# R284B.net
KiCad netlist of a schematic drawn in EAGLE
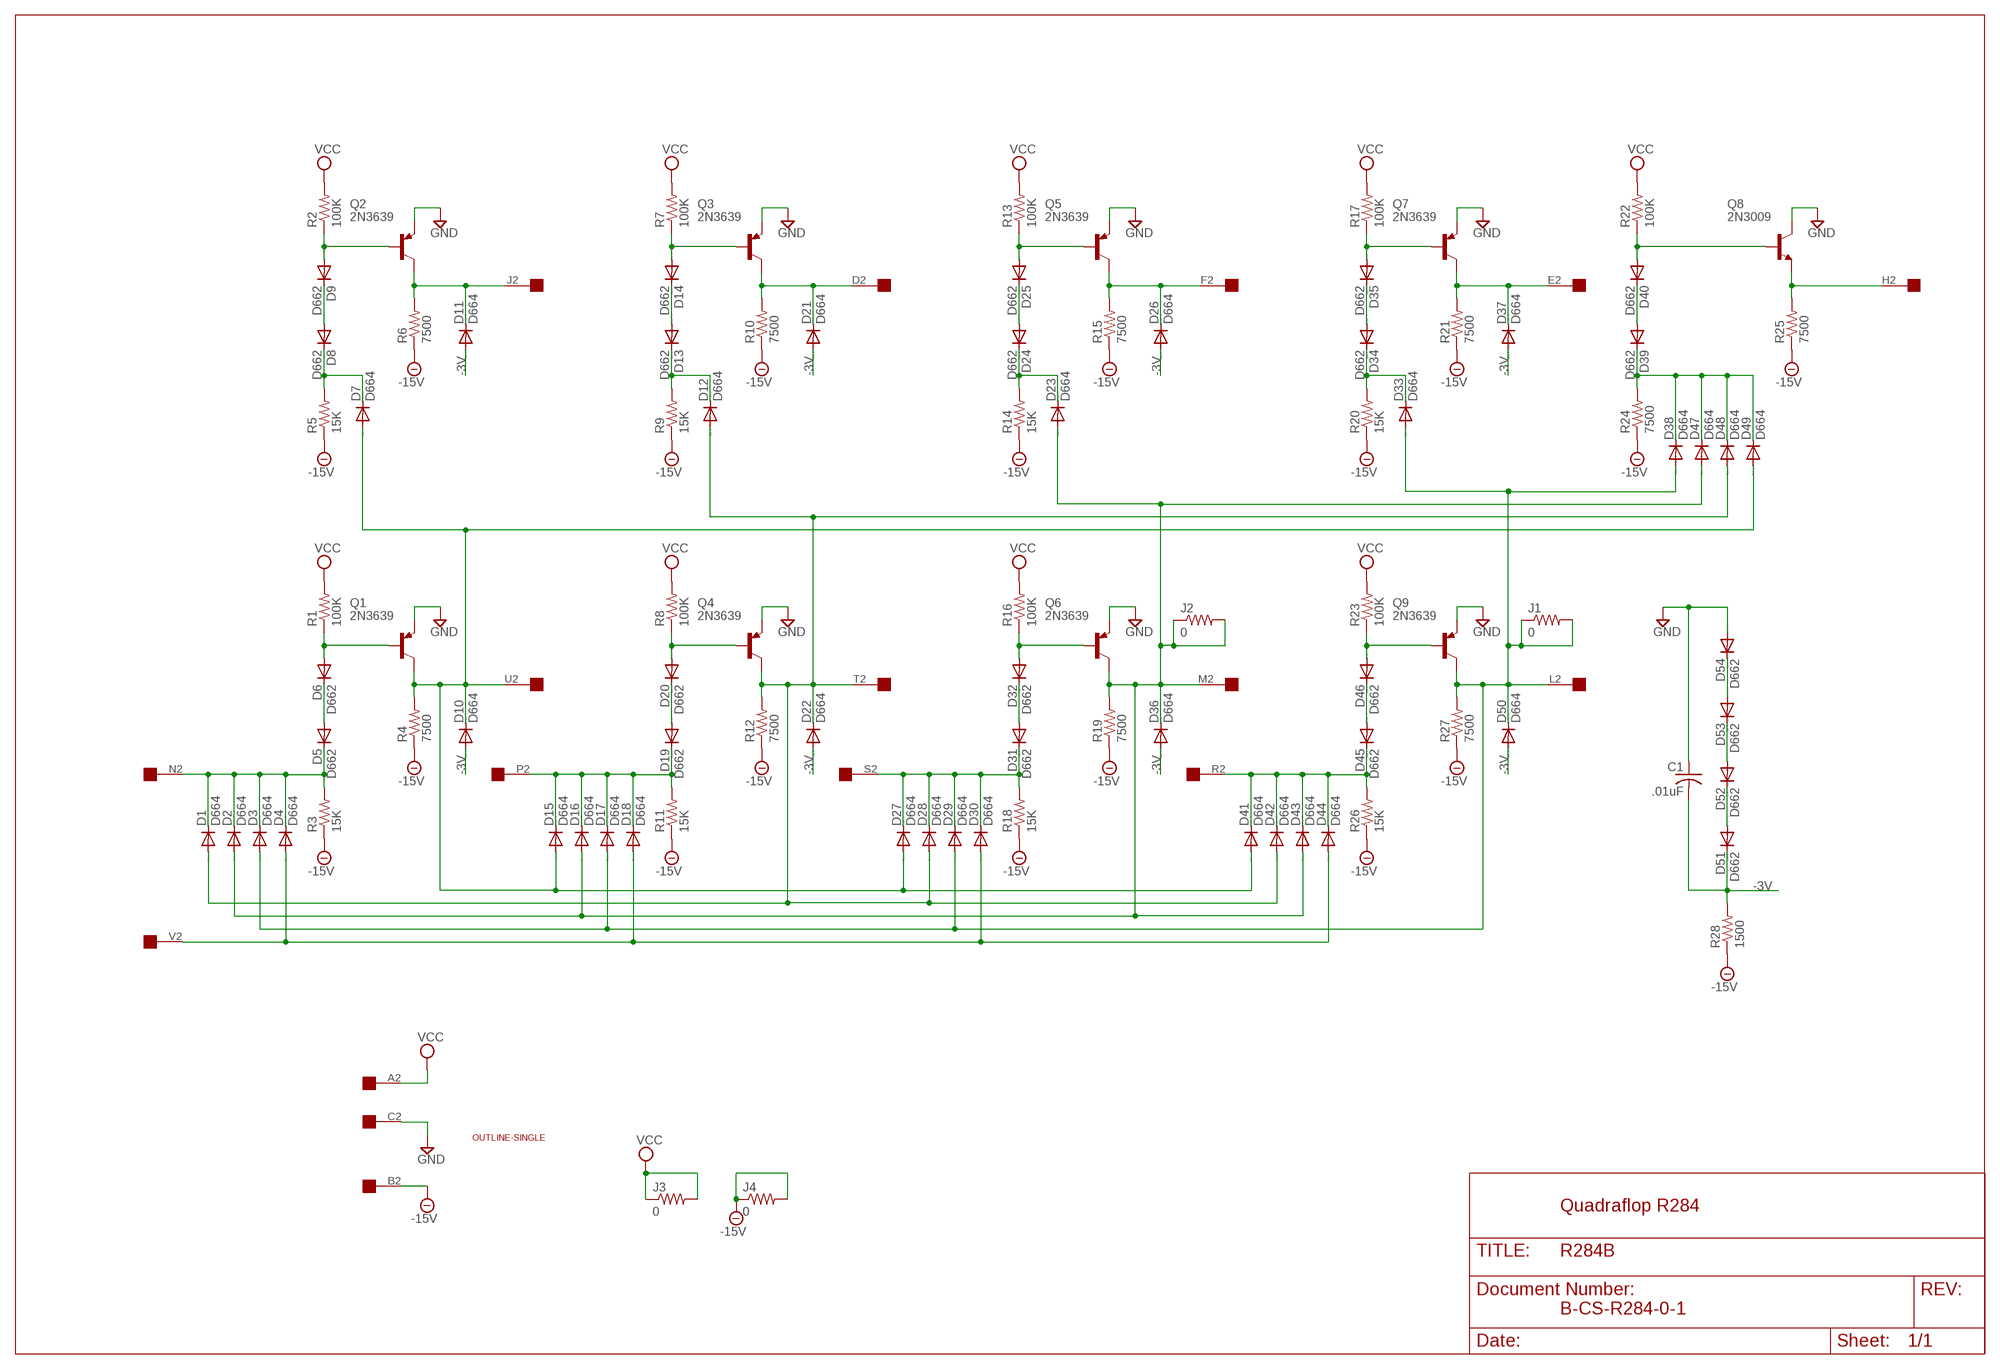
[diagram p0: schematic, sheet 1]

(export (version "E")
  (design (tool "Eeschema 10.0.6"))
  (components
    (comp (ref "C1")
      (value ".01uF")
      (footprint "eagle-import:C063-025X075")
      (libsource (lib "eagle-import") (part "C-US"))
    )
    (comp (ref "D1")
      (value "D664")
      (footprint "eagle-import:DO35-10")
      (libsource (lib "eagle-import") (part "DIODE-DO35-10"))
    )
    (comp (ref "D2")
      (value "D664")
      (footprint "eagle-import:DO35-10")
      (libsource (lib "eagle-import") (part "DIODE-DO35-10"))
    )
    (comp (ref "D3")
      (value "D664")
      (footprint "eagle-import:DO35-10")
      (libsource (lib "eagle-import") (part "DIODE-DO35-10"))
    )
    (comp (ref "D4")
      (value "D664")
      (footprint "eagle-import:DO35-10")
      (libsource (lib "eagle-import") (part "DIODE-DO35-10"))
    )
    (comp (ref "D5")
      (value "D662")
      (footprint "eagle-import:DO35-10")
      (libsource (lib "eagle-import") (part "DIODE-DO35-10"))
    )
    (comp (ref "D6")
      (value "D662")
      (footprint "eagle-import:DO35-10")
      (libsource (lib "eagle-import") (part "DIODE-DO35-10"))
    )
    (comp (ref "D7")
      (value "D664")
      (footprint "eagle-import:DO35-10")
      (libsource (lib "eagle-import") (part "DIODE-DO35-10"))
    )
    (comp (ref "D8")
      (value "D662")
      (footprint "eagle-import:DO35-10")
      (libsource (lib "eagle-import") (part "DIODE-DO35-10"))
    )
    (comp (ref "D9")
      (value "D662")
      (footprint "eagle-import:DO35-10")
      (libsource (lib "eagle-import") (part "DIODE-DO35-10"))
    )
    (comp (ref "D10")
      (value "D664")
      (footprint "eagle-import:DO35-10")
      (libsource (lib "eagle-import") (part "DIODE-DO35-10"))
    )
    (comp (ref "D11")
      (value "D664")
      (footprint "eagle-import:DO35-10")
      (libsource (lib "eagle-import") (part "DIODE-DO35-10"))
    )
    (comp (ref "D12")
      (value "D664")
      (footprint "eagle-import:DO35-10")
      (libsource (lib "eagle-import") (part "DIODE-DO35-10"))
    )
    (comp (ref "D13")
      (value "D662")
      (footprint "eagle-import:DO35-10")
      (libsource (lib "eagle-import") (part "DIODE-DO35-10"))
    )
    (comp (ref "D14")
      (value "D662")
      (footprint "eagle-import:DO35-10")
      (libsource (lib "eagle-import") (part "DIODE-DO35-10"))
    )
    (comp (ref "D15")
      (value "D664")
      (footprint "eagle-import:DO35-10")
      (libsource (lib "eagle-import") (part "DIODE-DO35-10"))
    )
    (comp (ref "D16")
      (value "D664")
      (footprint "eagle-import:DO35-10")
      (libsource (lib "eagle-import") (part "DIODE-DO35-10"))
    )
    (comp (ref "D17")
      (value "D664")
      (footprint "eagle-import:DO35-10")
      (libsource (lib "eagle-import") (part "DIODE-DO35-10"))
    )
    (comp (ref "D18")
      (value "D664")
      (footprint "eagle-import:DO35-10")
      (libsource (lib "eagle-import") (part "DIODE-DO35-10"))
    )
    (comp (ref "D19")
      (value "D662")
      (footprint "eagle-import:DO35-10")
      (libsource (lib "eagle-import") (part "DIODE-DO35-10"))
    )
    (comp (ref "D20")
      (value "D662")
      (footprint "eagle-import:DO35-10")
      (libsource (lib "eagle-import") (part "DIODE-DO35-10"))
    )
    (comp (ref "D21")
      (value "D664")
      (footprint "eagle-import:DO35-10")
      (libsource (lib "eagle-import") (part "DIODE-DO35-10"))
    )
    (comp (ref "D22")
      (value "D664")
      (footprint "eagle-import:DO35-10")
      (libsource (lib "eagle-import") (part "DIODE-DO35-10"))
    )
    (comp (ref "D23")
      (value "D664")
      (footprint "eagle-import:DO35-10")
      (libsource (lib "eagle-import") (part "DIODE-DO35-10"))
    )
    (comp (ref "D24")
      (value "D662")
      (footprint "eagle-import:DO35-10")
      (libsource (lib "eagle-import") (part "DIODE-DO35-10"))
    )
    (comp (ref "D25")
      (value "D662")
      (footprint "eagle-import:DO35-10")
      (libsource (lib "eagle-import") (part "DIODE-DO35-10"))
    )
    (comp (ref "D26")
      (value "D664")
      (footprint "eagle-import:DO35-10")
      (libsource (lib "eagle-import") (part "DIODE-DO35-10"))
    )
    (comp (ref "D27")
      (value "D664")
      (footprint "eagle-import:DO35-10")
      (libsource (lib "eagle-import") (part "DIODE-DO35-10"))
    )
    (comp (ref "D28")
      (value "D664")
      (footprint "eagle-import:DO35-10")
      (libsource (lib "eagle-import") (part "DIODE-DO35-10"))
    )
    (comp (ref "D29")
      (value "D664")
      (footprint "eagle-import:DO35-10")
      (libsource (lib "eagle-import") (part "DIODE-DO35-10"))
    )
    (comp (ref "D30")
      (value "D664")
      (footprint "eagle-import:DO35-10")
      (libsource (lib "eagle-import") (part "DIODE-DO35-10"))
    )
    (comp (ref "D31")
      (value "D662")
      (footprint "eagle-import:DO35-10")
      (libsource (lib "eagle-import") (part "DIODE-DO35-10"))
    )
    (comp (ref "D32")
      (value "D662")
      (footprint "eagle-import:DO35-10")
      (libsource (lib "eagle-import") (part "DIODE-DO35-10"))
    )
    (comp (ref "D33")
      (value "D664")
      (footprint "eagle-import:DO35-10")
      (libsource (lib "eagle-import") (part "DIODE-DO35-10"))
    )
    (comp (ref "D34")
      (value "D662")
      (footprint "eagle-import:DO35-10")
      (libsource (lib "eagle-import") (part "DIODE-DO35-10"))
    )
    (comp (ref "D35")
      (value "D662")
      (footprint "eagle-import:DO35-10")
      (libsource (lib "eagle-import") (part "DIODE-DO35-10"))
    )
    (comp (ref "D36")
      (value "D664")
      (footprint "eagle-import:DO35-10")
      (libsource (lib "eagle-import") (part "DIODE-DO35-10"))
    )
    (comp (ref "D37")
      (value "D664")
      (footprint "eagle-import:DO35-10")
      (libsource (lib "eagle-import") (part "DIODE-DO35-10"))
    )
    (comp (ref "D38")
      (value "D664")
      (footprint "eagle-import:DO35-10")
      (libsource (lib "eagle-import") (part "DIODE-DO35-10"))
    )
    (comp (ref "D39")
      (value "D662")
      (footprint "eagle-import:DO35-10")
      (libsource (lib "eagle-import") (part "DIODE-DO35-10"))
    )
    (comp (ref "D40")
      (value "D662")
      (footprint "eagle-import:DO35-10")
      (libsource (lib "eagle-import") (part "DIODE-DO35-10"))
    )
    (comp (ref "D41")
      (value "D664")
      (footprint "eagle-import:DO35-10")
      (libsource (lib "eagle-import") (part "DIODE-DO35-10"))
    )
    (comp (ref "D42")
      (value "D664")
      (footprint "eagle-import:DO35-10")
      (libsource (lib "eagle-import") (part "DIODE-DO35-10"))
    )
    (comp (ref "D43")
      (value "D664")
      (footprint "eagle-import:DO35-10")
      (libsource (lib "eagle-import") (part "DIODE-DO35-10"))
    )
    (comp (ref "D44")
      (value "D664")
      (footprint "eagle-import:DO35-10")
      (libsource (lib "eagle-import") (part "DIODE-DO35-10"))
    )
    (comp (ref "D45")
      (value "D662")
      (footprint "eagle-import:DO35-10")
      (libsource (lib "eagle-import") (part "DIODE-DO35-10"))
    )
    (comp (ref "D46")
      (value "D662")
      (footprint "eagle-import:DO35-10")
      (libsource (lib "eagle-import") (part "DIODE-DO35-10"))
    )
    (comp (ref "D47")
      (value "D664")
      (footprint "eagle-import:DO35-10")
      (libsource (lib "eagle-import") (part "DIODE-DO35-10"))
    )
    (comp (ref "D48")
      (value "D664")
      (footprint "eagle-import:DO35-10")
      (libsource (lib "eagle-import") (part "DIODE-DO35-10"))
    )
    (comp (ref "D49")
      (value "D664")
      (footprint "eagle-import:DO35-10")
      (libsource (lib "eagle-import") (part "DIODE-DO35-10"))
    )
    (comp (ref "D50")
      (value "D664")
      (footprint "eagle-import:DO35-10")
      (libsource (lib "eagle-import") (part "DIODE-DO35-10"))
    )
    (comp (ref "D51")
      (value "D662")
      (footprint "eagle-import:DO35-10")
      (libsource (lib "eagle-import") (part "DIODE-DO35-10"))
    )
    (comp (ref "D52")
      (value "D662")
      (footprint "eagle-import:DO35-10")
      (libsource (lib "eagle-import") (part "DIODE-DO35-10"))
    )
    (comp (ref "D53")
      (value "D662")
      (footprint "eagle-import:DO35-10")
      (libsource (lib "eagle-import") (part "DIODE-DO35-10"))
    )
    (comp (ref "D54")
      (value "D662")
      (footprint "eagle-import:DO35-10")
      (libsource (lib "eagle-import") (part "DIODE-DO35-10"))
    )
    (comp (ref "J1")
      (value "0")
      (footprint "eagle-import:0207_10")
      (libsource (lib "eagle-import") (part "R-US_0207/10"))
    )
    (comp (ref "J2")
      (value "0")
      (footprint "eagle-import:0207_10")
      (libsource (lib "eagle-import") (part "R-US_0207/10"))
    )
    (comp (ref "J3")
      (value "0")
      (footprint "eagle-import:0207_10")
      (libsource (lib "eagle-import") (part "R-US_0207/10"))
    )
    (comp (ref "J4")
      (value "0")
      (footprint "eagle-import:0207_10")
      (libsource (lib "eagle-import") (part "R-US_0207/10"))
    )
    (comp (ref "Q1")
      (value "2N3639")
      (footprint "eagle-import:TO5")
      (libsource (lib "eagle-import") (part "-PNP-TO5"))
    )
    (comp (ref "Q2")
      (value "2N3639")
      (footprint "eagle-import:TO5")
      (libsource (lib "eagle-import") (part "-PNP-TO5"))
    )
    (comp (ref "Q3")
      (value "2N3639")
      (footprint "eagle-import:TO5")
      (libsource (lib "eagle-import") (part "-PNP-TO5"))
    )
    (comp (ref "Q4")
      (value "2N3639")
      (footprint "eagle-import:TO5")
      (libsource (lib "eagle-import") (part "-PNP-TO5"))
    )
    (comp (ref "Q5")
      (value "2N3639")
      (footprint "eagle-import:TO5")
      (libsource (lib "eagle-import") (part "-PNP-TO5"))
    )
    (comp (ref "Q6")
      (value "2N3639")
      (footprint "eagle-import:TO5")
      (libsource (lib "eagle-import") (part "-PNP-TO5"))
    )
    (comp (ref "Q7")
      (value "2N3639")
      (footprint "eagle-import:TO5")
      (libsource (lib "eagle-import") (part "-PNP-TO5"))
    )
    (comp (ref "Q8")
      (value "2N3009")
      (footprint "eagle-import:TO5")
      (libsource (lib "eagle-import") (part "-NPN-TO5"))
    )
    (comp (ref "Q9")
      (value "2N3639")
      (footprint "eagle-import:TO5")
      (libsource (lib "eagle-import") (part "-PNP-TO5"))
    )
    (comp (ref "R1")
      (value "100K")
      (footprint "eagle-import:0207_10")
      (libsource (lib "eagle-import") (part "R-US_0207/10"))
    )
    (comp (ref "R2")
      (value "100K")
      (footprint "eagle-import:0207_10")
      (libsource (lib "eagle-import") (part "R-US_0207/10"))
    )
    (comp (ref "R3")
      (value "15K")
      (footprint "eagle-import:0207_10")
      (libsource (lib "eagle-import") (part "R-US_0207/10"))
    )
    (comp (ref "R4")
      (value "7500")
      (footprint "eagle-import:0207_10")
      (libsource (lib "eagle-import") (part "R-US_0207/10"))
    )
    (comp (ref "R5")
      (value "15K")
      (footprint "eagle-import:0207_10")
      (libsource (lib "eagle-import") (part "R-US_0207/10"))
    )
    (comp (ref "R6")
      (value "7500")
      (footprint "eagle-import:0207_10")
      (libsource (lib "eagle-import") (part "R-US_0207/10"))
    )
    (comp (ref "R7")
      (value "100K")
      (footprint "eagle-import:0207_10")
      (libsource (lib "eagle-import") (part "R-US_0207/10"))
    )
    (comp (ref "R8")
      (value "100K")
      (footprint "eagle-import:0207_10")
      (libsource (lib "eagle-import") (part "R-US_0207/10"))
    )
    (comp (ref "R9")
      (value "15K")
      (footprint "eagle-import:0207_10")
      (libsource (lib "eagle-import") (part "R-US_0207/10"))
    )
    (comp (ref "R10")
      (value "7500")
      (footprint "eagle-import:0207_10")
      (libsource (lib "eagle-import") (part "R-US_0207/10"))
    )
    (comp (ref "R11")
      (value "15K")
      (footprint "eagle-import:0207_10")
      (libsource (lib "eagle-import") (part "R-US_0207/10"))
    )
    (comp (ref "R12")
      (value "7500")
      (footprint "eagle-import:0207_10")
      (libsource (lib "eagle-import") (part "R-US_0207/10"))
    )
    (comp (ref "R13")
      (value "100K")
      (footprint "eagle-import:0207_10")
      (libsource (lib "eagle-import") (part "R-US_0207/10"))
    )
    (comp (ref "R14")
      (value "15K")
      (footprint "eagle-import:0207_10")
      (libsource (lib "eagle-import") (part "R-US_0207/10"))
    )
    (comp (ref "R15")
      (value "7500")
      (footprint "eagle-import:0207_10")
      (libsource (lib "eagle-import") (part "R-US_0207/10"))
    )
    (comp (ref "R16")
      (value "100K")
      (footprint "eagle-import:0207_10")
      (libsource (lib "eagle-import") (part "R-US_0207/10"))
    )
    (comp (ref "R17")
      (value "100K")
      (footprint "eagle-import:0207_10")
      (libsource (lib "eagle-import") (part "R-US_0207/10"))
    )
    (comp (ref "R18")
      (value "15K")
      (footprint "eagle-import:0207_10")
      (libsource (lib "eagle-import") (part "R-US_0207/10"))
    )
    (comp (ref "R19")
      (value "7500")
      (footprint "eagle-import:0207_10")
      (libsource (lib "eagle-import") (part "R-US_0207/10"))
    )
    (comp (ref "R20")
      (value "15K")
      (footprint "eagle-import:0207_10")
      (libsource (lib "eagle-import") (part "R-US_0207/10"))
    )
    (comp (ref "R21")
      (value "7500")
      (footprint "eagle-import:0207_10")
      (libsource (lib "eagle-import") (part "R-US_0207/10"))
    )
    (comp (ref "R22")
      (value "100K")
      (footprint "eagle-import:0207_10")
      (libsource (lib "eagle-import") (part "R-US_0207/10"))
    )
    (comp (ref "R23")
      (value "100K")
      (footprint "eagle-import:0207_10")
      (libsource (lib "eagle-import") (part "R-US_0207/10"))
    )
    (comp (ref "R24")
      (value "7500")
      (footprint "eagle-import:0207_10")
      (libsource (lib "eagle-import") (part "R-US_0207/10"))
    )
    (comp (ref "R25")
      (value "7500")
      (footprint "eagle-import:0207_10")
      (libsource (lib "eagle-import") (part "R-US_0207/10"))
    )
    (comp (ref "R26")
      (value "15K")
      (footprint "eagle-import:0207_10")
      (libsource (lib "eagle-import") (part "R-US_0207/10"))
    )
    (comp (ref "R27")
      (value "7500")
      (footprint "eagle-import:0207_10")
      (libsource (lib "eagle-import") (part "R-US_0207/10"))
    )
    (comp (ref "R28")
      (value "1500")
      (footprint "eagle-import:0207_10")
      (libsource (lib "eagle-import") (part "R-US_0207/10"))
    )
    (comp (ref "U$1")
      (value "OUTLINE-SINGLE")
      (footprint "eagle-import:SINGLE")
      (libsource (lib "eagle-import") (part "OUTLINE-SINGLE"))
    )
    (comp (ref "U$2")
      (value "EDGE-1")
      (footprint "eagle-import:EDGE-CON1")
      (libsource (lib "eagle-import") (part "EDGE-1"))
    )
  )
  (nets
    (net (code "1") (name "-15V") (class "Default")
      (node (ref "J4") (pin "1") (pinfunction "1_1") (pintype "passive"))
      (node (ref "J4") (pin "2") (pinfunction "2_2") (pintype "passive"))
      (node (ref "R10") (pin "1") (pinfunction "1_1") (pintype "passive"))
      (node (ref "R11") (pin "1") (pinfunction "1_1") (pintype "passive"))
      (node (ref "R12") (pin "1") (pinfunction "1_1") (pintype "passive"))
      (node (ref "R14") (pin "1") (pinfunction "1_1") (pintype "passive"))
      (node (ref "R15") (pin "1") (pinfunction "1_1") (pintype "passive"))
      (node (ref "R18") (pin "1") (pinfunction "1_1") (pintype "passive"))
      (node (ref "R19") (pin "1") (pinfunction "1_1") (pintype "passive"))
      (node (ref "R20") (pin "1") (pinfunction "1_1") (pintype "passive"))
      (node (ref "R21") (pin "1") (pinfunction "1_1") (pintype "passive"))
      (node (ref "R24") (pin "1") (pinfunction "1_1") (pintype "passive"))
      (node (ref "R25") (pin "1") (pinfunction "1_1") (pintype "passive"))
      (node (ref "R26") (pin "1") (pinfunction "1_1") (pintype "passive"))
      (node (ref "R27") (pin "1") (pinfunction "1_1") (pintype "passive"))
      (node (ref "R28") (pin "1") (pinfunction "1_1") (pintype "passive"))
      (node (ref "R3") (pin "1") (pinfunction "1_1") (pintype "passive"))
      (node (ref "R4") (pin "1") (pinfunction "1_1") (pintype "passive"))
      (node (ref "R5") (pin "1") (pinfunction "1_1") (pintype "passive"))
      (node (ref "R6") (pin "1") (pinfunction "1_1") (pintype "passive"))
      (node (ref "R9") (pin "1") (pinfunction "1_1") (pintype "passive"))
      (node (ref "U$2") (pin "B2") (pinfunction "1_B2") (pintype "bidirectional"))
    )
    (net (code "2") (name "/-3V") (class "Default")
      (node (ref "C1") (pin "2") (pinfunction "2_2") (pintype "passive"))
      (node (ref "D10") (pin "A") (pinfunction "A_A") (pintype "passive"))
      (node (ref "D11") (pin "A") (pinfunction "A_A") (pintype "passive"))
      (node (ref "D21") (pin "A") (pinfunction "A_A") (pintype "passive"))
      (node (ref "D22") (pin "A") (pinfunction "A_A") (pintype "passive"))
      (node (ref "D26") (pin "A") (pinfunction "A_A") (pintype "passive"))
      (node (ref "D36") (pin "A") (pinfunction "A_A") (pintype "passive"))
      (node (ref "D37") (pin "A") (pinfunction "A_A") (pintype "passive"))
      (node (ref "D50") (pin "A") (pinfunction "A_A") (pintype "passive"))
      (node (ref "D51") (pin "C") (pinfunction "C_C") (pintype "passive"))
      (node (ref "R28") (pin "2") (pinfunction "2_2") (pintype "passive"))
    )
    (net (code "3") (name "GND") (class "Default")
      (node (ref "C1") (pin "1") (pinfunction "1_1") (pintype "passive"))
      (node (ref "D54") (pin "A") (pinfunction "A_A") (pintype "passive"))
      (node (ref "Q1") (pin "1") (pinfunction "E_1") (pintype "passive"))
      (node (ref "Q2") (pin "1") (pinfunction "E_1") (pintype "passive"))
      (node (ref "Q3") (pin "1") (pinfunction "E_1") (pintype "passive"))
      (node (ref "Q4") (pin "1") (pinfunction "E_1") (pintype "passive"))
      (node (ref "Q5") (pin "1") (pinfunction "E_1") (pintype "passive"))
      (node (ref "Q6") (pin "1") (pinfunction "E_1") (pintype "passive"))
      (node (ref "Q7") (pin "1") (pinfunction "E_1") (pintype "passive"))
      (node (ref "Q8") (pin "3") (pinfunction "C_3") (pintype "passive"))
      (node (ref "Q9") (pin "1") (pinfunction "E_1") (pintype "passive"))
      (node (ref "U$2") (pin "C2") (pinfunction "1_C2") (pintype "bidirectional"))
    )
    (net (code "4") (name "Net-(D5-PadA)") (class "Default")
      (node (ref "D5") (pin "A") (pinfunction "A_A") (pintype "passive"))
      (node (ref "D6") (pin "C") (pinfunction "C_C") (pintype "passive"))
    )
    (net (code "5") (name "Net-(D7-PadC)") (class "Default")
      (node (ref "D7") (pin "C") (pinfunction "C_C") (pintype "passive"))
      (node (ref "D8") (pin "C") (pinfunction "C_C") (pintype "passive"))
      (node (ref "R5") (pin "2") (pinfunction "2_2") (pintype "passive"))
    )
    (net (code "6") (name "Net-(D8-PadA)") (class "Default")
      (node (ref "D8") (pin "A") (pinfunction "A_A") (pintype "passive"))
      (node (ref "D9") (pin "C") (pinfunction "C_C") (pintype "passive"))
    )
    (net (code "7") (name "Net-(D12-PadC)") (class "Default")
      (node (ref "D12") (pin "C") (pinfunction "C_C") (pintype "passive"))
      (node (ref "D13") (pin "C") (pinfunction "C_C") (pintype "passive"))
      (node (ref "R9") (pin "2") (pinfunction "2_2") (pintype "passive"))
    )
    (net (code "8") (name "Net-(D13-PadA)") (class "Default")
      (node (ref "D13") (pin "A") (pinfunction "A_A") (pintype "passive"))
      (node (ref "D14") (pin "C") (pinfunction "C_C") (pintype "passive"))
    )
    (net (code "9") (name "Net-(D19-PadA)") (class "Default")
      (node (ref "D19") (pin "A") (pinfunction "A_A") (pintype "passive"))
      (node (ref "D20") (pin "C") (pinfunction "C_C") (pintype "passive"))
    )
    (net (code "10") (name "Net-(D23-PadC)") (class "Default")
      (node (ref "D23") (pin "C") (pinfunction "C_C") (pintype "passive"))
      (node (ref "D24") (pin "C") (pinfunction "C_C") (pintype "passive"))
      (node (ref "R14") (pin "2") (pinfunction "2_2") (pintype "passive"))
    )
    (net (code "11") (name "Net-(D24-PadA)") (class "Default")
      (node (ref "D24") (pin "A") (pinfunction "A_A") (pintype "passive"))
      (node (ref "D25") (pin "C") (pinfunction "C_C") (pintype "passive"))
    )
    (net (code "12") (name "Net-(D31-PadA)") (class "Default")
      (node (ref "D31") (pin "A") (pinfunction "A_A") (pintype "passive"))
      (node (ref "D32") (pin "C") (pinfunction "C_C") (pintype "passive"))
    )
    (net (code "13") (name "Net-(D33-PadC)") (class "Default")
      (node (ref "D33") (pin "C") (pinfunction "C_C") (pintype "passive"))
      (node (ref "D34") (pin "C") (pinfunction "C_C") (pintype "passive"))
      (node (ref "R20") (pin "2") (pinfunction "2_2") (pintype "passive"))
    )
    (net (code "14") (name "Net-(D34-PadA)") (class "Default")
      (node (ref "D34") (pin "A") (pinfunction "A_A") (pintype "passive"))
      (node (ref "D35") (pin "C") (pinfunction "C_C") (pintype "passive"))
    )
    (net (code "15") (name "Net-(D38-PadC)") (class "Default")
      (node (ref "D38") (pin "C") (pinfunction "C_C") (pintype "passive"))
      (node (ref "D39") (pin "C") (pinfunction "C_C") (pintype "passive"))
      (node (ref "D47") (pin "C") (pinfunction "C_C") (pintype "passive"))
      (node (ref "D48") (pin "C") (pinfunction "C_C") (pintype "passive"))
      (node (ref "D49") (pin "C") (pinfunction "C_C") (pintype "passive"))
      (node (ref "R24") (pin "2") (pinfunction "2_2") (pintype "passive"))
    )
    (net (code "16") (name "Net-(D39-PadA)") (class "Default")
      (node (ref "D39") (pin "A") (pinfunction "A_A") (pintype "passive"))
      (node (ref "D40") (pin "C") (pinfunction "C_C") (pintype "passive"))
    )
    (net (code "17") (name "Net-(D45-PadA)") (class "Default")
      (node (ref "D45") (pin "A") (pinfunction "A_A") (pintype "passive"))
      (node (ref "D46") (pin "C") (pinfunction "C_C") (pintype "passive"))
    )
    (net (code "18") (name "Net-(D51-PadA)") (class "Default")
      (node (ref "D51") (pin "A") (pinfunction "A_A") (pintype "passive"))
      (node (ref "D52") (pin "C") (pinfunction "C_C") (pintype "passive"))
    )
    (net (code "19") (name "Net-(D52-PadA)") (class "Default")
      (node (ref "D52") (pin "A") (pinfunction "A_A") (pintype "passive"))
      (node (ref "D53") (pin "C") (pinfunction "C_C") (pintype "passive"))
    )
    (net (code "20") (name "Net-(D53-PadA)") (class "Default")
      (node (ref "D53") (pin "A") (pinfunction "A_A") (pintype "passive"))
      (node (ref "D54") (pin "C") (pinfunction "C_C") (pintype "passive"))
    )
    (net (code "21") (name "Net-(Q1-B)") (class "Default")
      (node (ref "D6") (pin "A") (pinfunction "A_A") (pintype "passive"))
      (node (ref "Q1") (pin "2") (pinfunction "B_2") (pintype "passive"))
      (node (ref "R1") (pin "1") (pinfunction "1_1") (pintype "passive"))
    )
    (net (code "22") (name "Net-(Q1-C)") (class "Default")
      (node (ref "D10") (pin "C") (pinfunction "C_C") (pintype "passive"))
      (node (ref "D15") (pin "A") (pinfunction "A_A") (pintype "passive"))
      (node (ref "D27") (pin "A") (pinfunction "A_A") (pintype "passive"))
      (node (ref "D41") (pin "A") (pinfunction "A_A") (pintype "passive"))
      (node (ref "D49") (pin "A") (pinfunction "A_A") (pintype "passive"))
      (node (ref "D7") (pin "A") (pinfunction "A_A") (pintype "passive"))
      (node (ref "Q1") (pin "3") (pinfunction "C_3") (pintype "passive"))
      (node (ref "R4") (pin "2") (pinfunction "2_2") (pintype "passive"))
      (node (ref "U$2") (pin "U2") (pinfunction "1_U2") (pintype "bidirectional"))
    )
    (net (code "23") (name "Net-(Q2-B)") (class "Default")
      (node (ref "D9") (pin "A") (pinfunction "A_A") (pintype "passive"))
      (node (ref "Q2") (pin "2") (pinfunction "B_2") (pintype "passive"))
      (node (ref "R2") (pin "1") (pinfunction "1_1") (pintype "passive"))
    )
    (net (code "24") (name "Net-(Q2-C)") (class "Default")
      (node (ref "D11") (pin "C") (pinfunction "C_C") (pintype "passive"))
      (node (ref "Q2") (pin "3") (pinfunction "C_3") (pintype "passive"))
      (node (ref "R6") (pin "2") (pinfunction "2_2") (pintype "passive"))
      (node (ref "U$2") (pin "J2") (pinfunction "1_J2") (pintype "bidirectional"))
    )
    (net (code "25") (name "Net-(Q3-B)") (class "Default")
      (node (ref "D14") (pin "A") (pinfunction "A_A") (pintype "passive"))
      (node (ref "Q3") (pin "2") (pinfunction "B_2") (pintype "passive"))
      (node (ref "R7") (pin "1") (pinfunction "1_1") (pintype "passive"))
    )
    (net (code "26") (name "Net-(Q3-C)") (class "Default")
      (node (ref "D21") (pin "C") (pinfunction "C_C") (pintype "passive"))
      (node (ref "Q3") (pin "3") (pinfunction "C_3") (pintype "passive"))
      (node (ref "R10") (pin "2") (pinfunction "2_2") (pintype "passive"))
      (node (ref "U$2") (pin "D2") (pinfunction "1_D2") (pintype "bidirectional"))
    )
    (net (code "27") (name "Net-(Q4-B)") (class "Default")
      (node (ref "D20") (pin "A") (pinfunction "A_A") (pintype "passive"))
      (node (ref "Q4") (pin "2") (pinfunction "B_2") (pintype "passive"))
      (node (ref "R8") (pin "1") (pinfunction "1_1") (pintype "passive"))
    )
    (net (code "28") (name "Net-(Q4-C)") (class "Default")
      (node (ref "D1") (pin "A") (pinfunction "A_A") (pintype "passive"))
      (node (ref "D12") (pin "A") (pinfunction "A_A") (pintype "passive"))
      (node (ref "D22") (pin "C") (pinfunction "C_C") (pintype "passive"))
      (node (ref "D28") (pin "A") (pinfunction "A_A") (pintype "passive"))
      (node (ref "D42") (pin "A") (pinfunction "A_A") (pintype "passive"))
      (node (ref "D48") (pin "A") (pinfunction "A_A") (pintype "passive"))
      (node (ref "Q4") (pin "3") (pinfunction "C_3") (pintype "passive"))
      (node (ref "R12") (pin "2") (pinfunction "2_2") (pintype "passive"))
      (node (ref "U$2") (pin "T2") (pinfunction "1_T2") (pintype "bidirectional"))
    )
    (net (code "29") (name "Net-(Q5-B)") (class "Default")
      (node (ref "D25") (pin "A") (pinfunction "A_A") (pintype "passive"))
      (node (ref "Q5") (pin "2") (pinfunction "B_2") (pintype "passive"))
      (node (ref "R13") (pin "1") (pinfunction "1_1") (pintype "passive"))
    )
    (net (code "30") (name "Net-(Q5-C)") (class "Default")
      (node (ref "D26") (pin "C") (pinfunction "C_C") (pintype "passive"))
      (node (ref "Q5") (pin "3") (pinfunction "C_3") (pintype "passive"))
      (node (ref "R15") (pin "2") (pinfunction "2_2") (pintype "passive"))
      (node (ref "U$2") (pin "F2") (pinfunction "1_F2") (pintype "bidirectional"))
    )
    (net (code "31") (name "Net-(Q6-B)") (class "Default")
      (node (ref "D32") (pin "A") (pinfunction "A_A") (pintype "passive"))
      (node (ref "Q6") (pin "2") (pinfunction "B_2") (pintype "passive"))
      (node (ref "R16") (pin "1") (pinfunction "1_1") (pintype "passive"))
    )
    (net (code "32") (name "Net-(Q6-C)") (class "Default")
      (node (ref "D16") (pin "A") (pinfunction "A_A") (pintype "passive"))
      (node (ref "D2") (pin "A") (pinfunction "A_A") (pintype "passive"))
      (node (ref "D23") (pin "A") (pinfunction "A_A") (pintype "passive"))
      (node (ref "D36") (pin "C") (pinfunction "C_C") (pintype "passive"))
      (node (ref "D43") (pin "A") (pinfunction "A_A") (pintype "passive"))
      (node (ref "D47") (pin "A") (pinfunction "A_A") (pintype "passive"))
      (node (ref "J2") (pin "1") (pinfunction "1_1") (pintype "passive"))
      (node (ref "J2") (pin "2") (pinfunction "2_2") (pintype "passive"))
      (node (ref "Q6") (pin "3") (pinfunction "C_3") (pintype "passive"))
      (node (ref "R19") (pin "2") (pinfunction "2_2") (pintype "passive"))
      (node (ref "U$2") (pin "M2") (pinfunction "1_M2") (pintype "bidirectional"))
    )
    (net (code "33") (name "Net-(Q7-B)") (class "Default")
      (node (ref "D35") (pin "A") (pinfunction "A_A") (pintype "passive"))
      (node (ref "Q7") (pin "2") (pinfunction "B_2") (pintype "passive"))
      (node (ref "R17") (pin "1") (pinfunction "1_1") (pintype "passive"))
    )
    (net (code "34") (name "Net-(Q7-C)") (class "Default")
      (node (ref "D37") (pin "C") (pinfunction "C_C") (pintype "passive"))
      (node (ref "Q7") (pin "3") (pinfunction "C_3") (pintype "passive"))
      (node (ref "R21") (pin "2") (pinfunction "2_2") (pintype "passive"))
      (node (ref "U$2") (pin "E2") (pinfunction "1_E2") (pintype "bidirectional"))
    )
    (net (code "35") (name "Net-(Q8-B)") (class "Default")
      (node (ref "D40") (pin "A") (pinfunction "A_A") (pintype "passive"))
      (node (ref "Q8") (pin "2") (pinfunction "B_2") (pintype "passive"))
      (node (ref "R22") (pin "1") (pinfunction "1_1") (pintype "passive"))
    )
    (net (code "36") (name "Net-(Q8-E)") (class "Default")
      (node (ref "Q8") (pin "1") (pinfunction "E_1") (pintype "passive"))
      (node (ref "R25") (pin "2") (pinfunction "2_2") (pintype "passive"))
      (node (ref "U$2") (pin "H2") (pinfunction "1_H2") (pintype "bidirectional"))
    )
    (net (code "37") (name "Net-(Q9-B)") (class "Default")
      (node (ref "D46") (pin "A") (pinfunction "A_A") (pintype "passive"))
      (node (ref "Q9") (pin "2") (pinfunction "B_2") (pintype "passive"))
      (node (ref "R23") (pin "1") (pinfunction "1_1") (pintype "passive"))
    )
    (net (code "38") (name "Net-(Q9-C)") (class "Default")
      (node (ref "D17") (pin "A") (pinfunction "A_A") (pintype "passive"))
      (node (ref "D29") (pin "A") (pinfunction "A_A") (pintype "passive"))
      (node (ref "D3") (pin "A") (pinfunction "A_A") (pintype "passive"))
      (node (ref "D33") (pin "A") (pinfunction "A_A") (pintype "passive"))
      (node (ref "D38") (pin "A") (pinfunction "A_A") (pintype "passive"))
      (node (ref "D50") (pin "C") (pinfunction "C_C") (pintype "passive"))
      (node (ref "J1") (pin "1") (pinfunction "1_1") (pintype "passive"))
      (node (ref "J1") (pin "2") (pinfunction "2_2") (pintype "passive"))
      (node (ref "Q9") (pin "3") (pinfunction "C_3") (pintype "passive"))
      (node (ref "R27") (pin "2") (pinfunction "2_2") (pintype "passive"))
      (node (ref "U$2") (pin "L2") (pinfunction "1_L2") (pintype "bidirectional"))
    )
    (net (code "39") (name "Net-(U$2L-1)") (class "Default")
      (node (ref "D1") (pin "C") (pinfunction "C_C") (pintype "passive"))
      (node (ref "D2") (pin "C") (pinfunction "C_C") (pintype "passive"))
      (node (ref "D3") (pin "C") (pinfunction "C_C") (pintype "passive"))
      (node (ref "D4") (pin "C") (pinfunction "C_C") (pintype "passive"))
      (node (ref "D5") (pin "C") (pinfunction "C_C") (pintype "passive"))
      (node (ref "R3") (pin "2") (pinfunction "2_2") (pintype "passive"))
      (node (ref "U$2") (pin "N2") (pinfunction "1_N2") (pintype "bidirectional"))
    )
    (net (code "40") (name "Net-(U$2M-1)") (class "Default")
      (node (ref "D15") (pin "C") (pinfunction "C_C") (pintype "passive"))
      (node (ref "D16") (pin "C") (pinfunction "C_C") (pintype "passive"))
      (node (ref "D17") (pin "C") (pinfunction "C_C") (pintype "passive"))
      (node (ref "D18") (pin "C") (pinfunction "C_C") (pintype "passive"))
      (node (ref "D19") (pin "C") (pinfunction "C_C") (pintype "passive"))
      (node (ref "R11") (pin "2") (pinfunction "2_2") (pintype "passive"))
      (node (ref "U$2") (pin "P2") (pinfunction "1_P2") (pintype "bidirectional"))
    )
    (net (code "41") (name "Net-(U$2N-1)") (class "Default")
      (node (ref "D41") (pin "C") (pinfunction "C_C") (pintype "passive"))
      (node (ref "D42") (pin "C") (pinfunction "C_C") (pintype "passive"))
      (node (ref "D43") (pin "C") (pinfunction "C_C") (pintype "passive"))
      (node (ref "D44") (pin "C") (pinfunction "C_C") (pintype "passive"))
      (node (ref "D45") (pin "C") (pinfunction "C_C") (pintype "passive"))
      (node (ref "R26") (pin "2") (pinfunction "2_2") (pintype "passive"))
      (node (ref "U$2") (pin "R2") (pinfunction "1_R2") (pintype "bidirectional"))
    )
    (net (code "42") (name "Net-(U$2O-1)") (class "Default")
      (node (ref "D27") (pin "C") (pinfunction "C_C") (pintype "passive"))
      (node (ref "D28") (pin "C") (pinfunction "C_C") (pintype "passive"))
      (node (ref "D29") (pin "C") (pinfunction "C_C") (pintype "passive"))
      (node (ref "D30") (pin "C") (pinfunction "C_C") (pintype "passive"))
      (node (ref "D31") (pin "C") (pinfunction "C_C") (pintype "passive"))
      (node (ref "R18") (pin "2") (pinfunction "2_2") (pintype "passive"))
      (node (ref "U$2") (pin "S2") (pinfunction "1_S2") (pintype "bidirectional"))
    )
    (net (code "43") (name "Net-(U$2R-1)") (class "Default")
      (node (ref "D18") (pin "A") (pinfunction "A_A") (pintype "passive"))
      (node (ref "D30") (pin "A") (pinfunction "A_A") (pintype "passive"))
      (node (ref "D4") (pin "A") (pinfunction "A_A") (pintype "passive"))
      (node (ref "D44") (pin "A") (pinfunction "A_A") (pintype "passive"))
      (node (ref "U$2") (pin "V2") (pinfunction "1_V2") (pintype "bidirectional"))
    )
    (net (code "44") (name "VCC") (class "Default")
      (node (ref "J3") (pin "1") (pinfunction "1_1") (pintype "passive"))
      (node (ref "J3") (pin "2") (pinfunction "2_2") (pintype "passive"))
      (node (ref "R1") (pin "2") (pinfunction "2_2") (pintype "passive"))
      (node (ref "R13") (pin "2") (pinfunction "2_2") (pintype "passive"))
      (node (ref "R16") (pin "2") (pinfunction "2_2") (pintype "passive"))
      (node (ref "R17") (pin "2") (pinfunction "2_2") (pintype "passive"))
      (node (ref "R2") (pin "2") (pinfunction "2_2") (pintype "passive"))
      (node (ref "R22") (pin "2") (pinfunction "2_2") (pintype "passive"))
      (node (ref "R23") (pin "2") (pinfunction "2_2") (pintype "passive"))
      (node (ref "R7") (pin "2") (pinfunction "2_2") (pintype "passive"))
      (node (ref "R8") (pin "2") (pinfunction "2_2") (pintype "passive"))
      (node (ref "U$2") (pin "A2") (pinfunction "1_A2") (pintype "bidirectional"))
    )
  )
)
